# ActiTouch_Receiver_Sheet1.net
KiCad netlist of a schematic drawn in Altium Designer
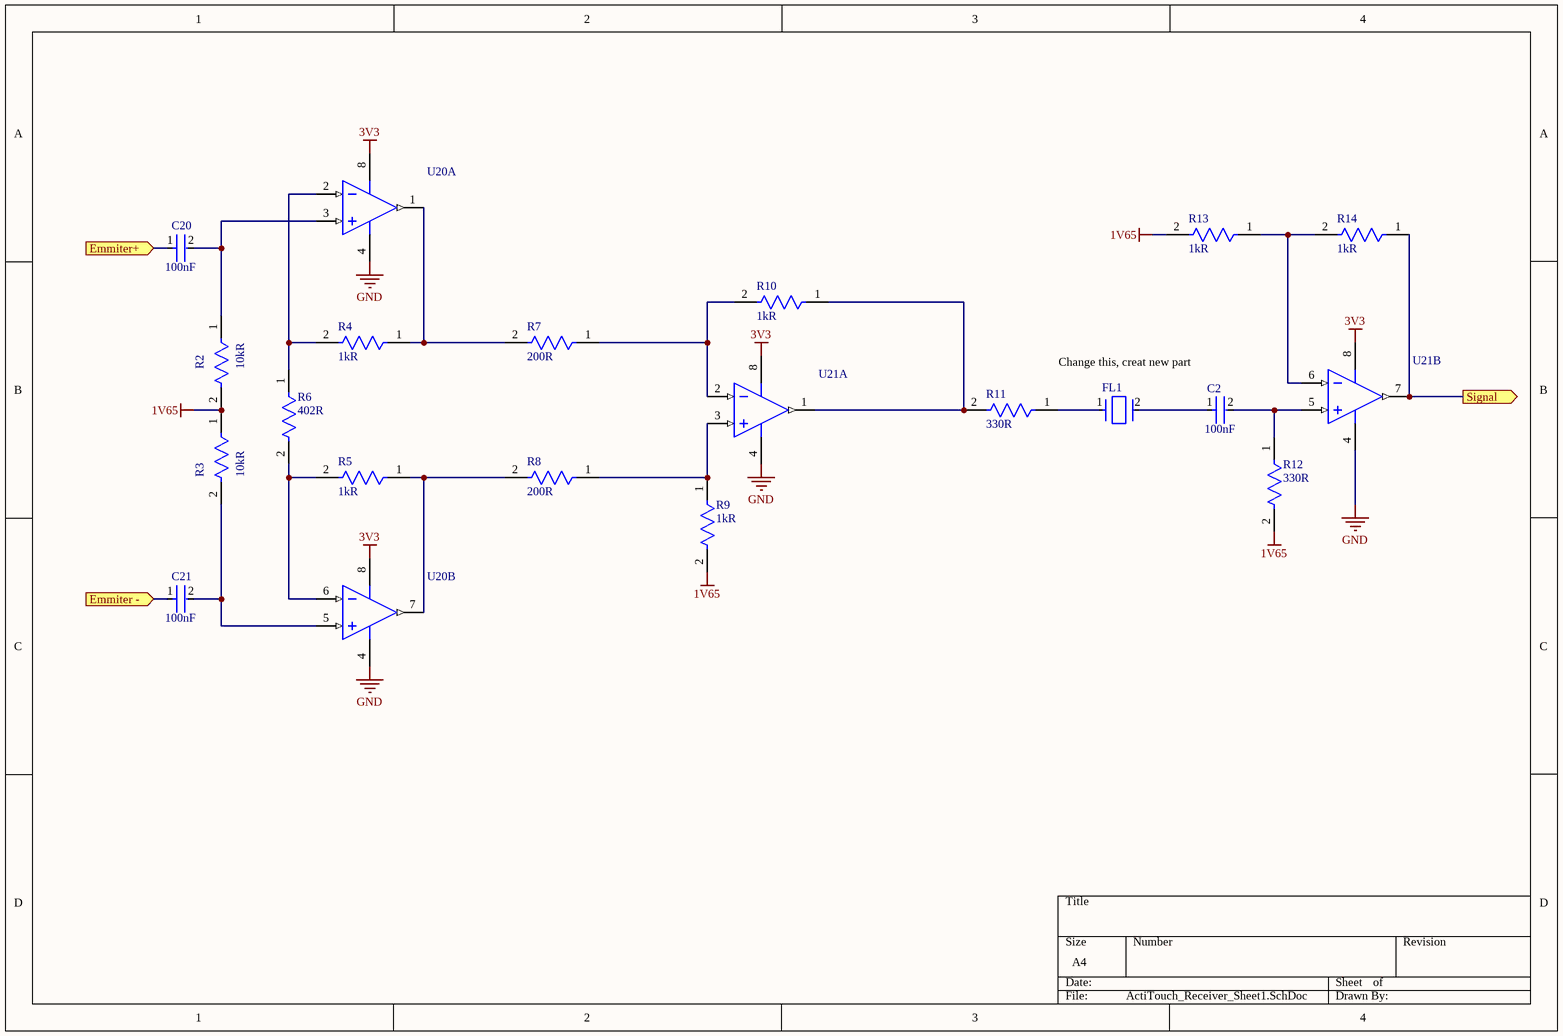
[diagram p0: ActiTouch_Receiver_Sheet1.SchDoc]

(export (version "E")
  (design (tool "Eeschema 10.0.6"))
  (components
    (comp (ref "C2")
      (value "EMK107B7104KAHT")
      (footprint "FP-0603-L_1_6_0_1-W_0_8_0-IPC_B")
      (description "None")
      (fields (field (name "CAPACITANCE") "100nF") (field (name "TOLERANCE") "10%"))
      (libsource (lib "Altium Content Vault") (part "02cd4be3c70576c341d710602a673aa"))
    )
    (comp (ref "C20")
      (value "EMK107B7104KAHT")
      (footprint "FP-0603-L_1_6_0_1-W_0_8_0-IPC_B")
      (description "None")
      (fields (field (name "CAPACITANCE") "100nF") (field (name "TOLERANCE") "10%"))
      (libsource (lib "Altium Content Vault") (part "02cd4be3c70576c341d710602a673aa"))
    )
    (comp (ref "C21")
      (value "EMK107B7104KAHT")
      (footprint "FP-0603-L_1_6_0_1-W_0_8_0-IPC_B")
      (description "None")
      (fields (field (name "CAPACITANCE") "100nF") (field (name "TOLERANCE") "10%"))
      (libsource (lib "Altium Content Vault") (part "02cd4be3c70576c341d710602a673aa"))
    )
    (comp (ref "FL1")
      (value "CDSCB10M7GA121-R0")
      (footprint "FP-CDSCB10M7GA121-R0-MFG")
      (description "Ceramic Filter 10.7MHz 2-Pin Surface Mount Emboss T/R")
      (libsource (lib "Altium Content Vault") (part "c23a69dc6c9e2f18f2079038eb95dd1"))
    )
    (comp (ref "R2")
      (value "ESR03EZPJ101")
      (footprint "FP-ESR03-MFG")
      (description "100Ω ±5% 0.25W 0603 Anti-Surge Chip Resistor AEC-Q200")
      (fields (field (name "TOLERANCE") "5%") (field (name "RESISTANCE") "10kR"))
      (libsource (lib "Altium Content Vault") (part "1029c3af85768c4190bb7ad29bc67b5"))
    )
    (comp (ref "R3")
      (value "ESR03EZPJ101")
      (footprint "FP-ESR03-MFG")
      (description "100Ω ±5% 0.25W 0603 Anti-Surge Chip Resistor AEC-Q200")
      (fields (field (name "TOLERANCE") "5%") (field (name "RESISTANCE") "10kR"))
      (libsource (lib "Altium Content Vault") (part "1029c3af85768c4190bb7ad29bc67b5"))
    )
    (comp (ref "R4")
      (value "ESR03EZPJ101")
      (footprint "FP-ESR03-MFG")
      (description "100Ω ±5% 0.25W 0603 Anti-Surge Chip Resistor AEC-Q200")
      (fields (field (name "TOLERANCE") "5%") (field (name "RESISTANCE") "1kR"))
      (libsource (lib "Altium Content Vault") (part "1029c3af85768c4190bb7ad29bc67b5"))
    )
    (comp (ref "R5")
      (value "ESR03EZPJ101")
      (footprint "FP-ESR03-MFG")
      (description "100Ω ±5% 0.25W 0603 Anti-Surge Chip Resistor AEC-Q200")
      (fields (field (name "TOLERANCE") "5%") (field (name "RESISTANCE") "1kR"))
      (libsource (lib "Altium Content Vault") (part "1029c3af85768c4190bb7ad29bc67b5"))
    )
    (comp (ref "R6")
      (value "ESR03EZPJ101")
      (footprint "FP-ESR03-MFG")
      (description "100Ω ±5% 0.25W 0603 Anti-Surge Chip Resistor AEC-Q200")
      (fields (field (name "TOLERANCE") "5%") (field (name "RESISTANCE") "402R"))
      (libsource (lib "Altium Content Vault") (part "1029c3af85768c4190bb7ad29bc67b5"))
    )
    (comp (ref "R7")
      (value "ESR03EZPJ101")
      (footprint "FP-ESR03-MFG")
      (description "100Ω ±5% 0.25W 0603 Anti-Surge Chip Resistor AEC-Q200")
      (fields (field (name "TOLERANCE") "5%") (field (name "RESISTANCE") "200R"))
      (libsource (lib "Altium Content Vault") (part "1029c3af85768c4190bb7ad29bc67b5"))
    )
    (comp (ref "R8")
      (value "ESR03EZPJ101")
      (footprint "FP-ESR03-MFG")
      (description "100Ω ±5% 0.25W 0603 Anti-Surge Chip Resistor AEC-Q200")
      (fields (field (name "TOLERANCE") "5%") (field (name "RESISTANCE") "200R"))
      (libsource (lib "Altium Content Vault") (part "1029c3af85768c4190bb7ad29bc67b5"))
    )
    (comp (ref "R9")
      (value "ESR03EZPJ101")
      (footprint "FP-ESR03-MFG")
      (description "100Ω ±5% 0.25W 0603 Anti-Surge Chip Resistor AEC-Q200")
      (fields (field (name "TOLERANCE") "5%") (field (name "RESISTANCE") "1kR"))
      (libsource (lib "Altium Content Vault") (part "1029c3af85768c4190bb7ad29bc67b5"))
    )
    (comp (ref "R10")
      (value "ESR03EZPJ101")
      (footprint "FP-ESR03-MFG")
      (description "100Ω ±5% 0.25W 0603 Anti-Surge Chip Resistor AEC-Q200")
      (fields (field (name "TOLERANCE") "5%") (field (name "RESISTANCE") "1kR"))
      (libsource (lib "Altium Content Vault") (part "1029c3af85768c4190bb7ad29bc67b5"))
    )
    (comp (ref "R11")
      (value "ESR03EZPJ101")
      (footprint "FP-ESR03-MFG")
      (description "100Ω ±5% 0.25W 0603 Anti-Surge Chip Resistor AEC-Q200")
      (fields (field (name "TOLERANCE") "5%") (field (name "RESISTANCE") "330R"))
      (libsource (lib "Altium Content Vault") (part "1029c3af85768c4190bb7ad29bc67b5"))
    )
    (comp (ref "R12")
      (value "ESR03EZPJ101")
      (footprint "FP-ESR03-MFG")
      (description "100Ω ±5% 0.25W 0603 Anti-Surge Chip Resistor AEC-Q200")
      (fields (field (name "TOLERANCE") "5%") (field (name "RESISTANCE") "330R"))
      (libsource (lib "Altium Content Vault") (part "1029c3af85768c4190bb7ad29bc67b5"))
    )
    (comp (ref "R13")
      (value "ESR03EZPJ101")
      (footprint "FP-ESR03-MFG")
      (description "100Ω ±5% 0.25W 0603 Anti-Surge Chip Resistor AEC-Q200")
      (fields (field (name "TOLERANCE") "5%") (field (name "RESISTANCE") "1kR"))
      (libsource (lib "Altium Content Vault") (part "1029c3af85768c4190bb7ad29bc67b5"))
    )
    (comp (ref "R14")
      (value "ESR03EZPJ101")
      (footprint "FP-ESR03-MFG")
      (description "100Ω ±5% 0.25W 0603 Anti-Surge Chip Resistor AEC-Q200")
      (fields (field (name "TOLERANCE") "5%") (field (name "RESISTANCE") "1kR"))
      (libsource (lib "Altium Content Vault") (part "1029c3af85768c4190bb7ad29bc67b5"))
    )
    (comp (ref "U20")
      (value "LTC6253IMS8#TRPBF")
      (footprint "LT-MS8-8_N")
      (fields
        (field (name "LINEAR TECHNOLOGY PART NUMBER") "LTC6253")
        (field (name "MANUFACTURER") "Linear Technology")
      )
      (libsource (lib "Altium Content Vault") (part "LT-LTC6253-MS8-8"))
    )
    (comp (ref "U21")
      (value "LTC6253IMS8#TRPBF")
      (footprint "LT-MS8-8_N")
      (fields
        (field (name "LINEAR TECHNOLOGY PART NUMBER") "LTC6253")
        (field (name "MANUFACTURER") "Linear Technology")
      )
      (libsource (lib "Altium Content Vault") (part "LT-LTC6253-MS8-8"))
    )
  )
  (nets
    (net (code "1") (name "/Emmiter -") (class "Default")
      (node (ref "C21") (pin "1") (pinfunction "1_1") (pintype "passive"))
    )
    (net (code "2") (name "/Emmiter+") (class "Default")
      (node (ref "C20") (pin "1") (pinfunction "1_1") (pintype "passive"))
    )
    (net (code "3") (name "/Signal") (class "Default")
      (node (ref "R14") (pin "1") (pinfunction "1_1") (pintype "passive"))
      (node (ref "U21") (pin "7") (pinfunction "OUT_B_7") (pintype "output"))
    )
    (net (code "4") (name "1V65") (class "Default")
      (node (ref "R12") (pin "2") (pinfunction "2_2") (pintype "passive"))
      (node (ref "R13") (pin "2") (pinfunction "2_2") (pintype "passive"))
      (node (ref "R2") (pin "2") (pinfunction "2_2") (pintype "passive"))
      (node (ref "R3") (pin "1") (pinfunction "1_1") (pintype "passive"))
      (node (ref "R9") (pin "2") (pinfunction "2_2") (pintype "passive"))
    )
    (net (code "5") (name "3V3") (class "Default")
      (node (ref "U20") (pin "8") (pinfunction "V+_8") (pintype "power_in"))
      (node (ref "U21") (pin "8") (pinfunction "V+_8") (pintype "power_in"))
    )
    (net (code "6") (name "GND") (class "Default")
      (node (ref "U20") (pin "4") (pinfunction "V-_4") (pintype "power_in"))
      (node (ref "U21") (pin "4") (pinfunction "V-_4") (pintype "power_in"))
    )
    (net (code "7") (name "Net-(C2-Pad1)") (class "Default")
      (node (ref "C2") (pin "1") (pinfunction "1_1") (pintype "passive"))
      (node (ref "FL1") (pin "2") (pinfunction "2_2") (pintype "passive"))
    )
    (net (code "8") (name "Net-(FL1-Pad1)") (class "Default")
      (node (ref "FL1") (pin "1") (pinfunction "1_1") (pintype "passive"))
      (node (ref "R11") (pin "1") (pinfunction "1_1") (pintype "passive"))
    )
    (net (code "9") (name "Net-(U20A-+IN_A)") (class "Default")
      (node (ref "C20") (pin "2") (pinfunction "2_2") (pintype "passive"))
      (node (ref "R2") (pin "1") (pinfunction "1_1") (pintype "passive"))
      (node (ref "U20") (pin "3") (pinfunction "+IN_A_3") (pintype "input"))
    )
    (net (code "10") (name "Net-(U20A--IN_A)") (class "Default")
      (node (ref "R4") (pin "2") (pinfunction "2_2") (pintype "passive"))
      (node (ref "R6") (pin "1") (pinfunction "1_1") (pintype "passive"))
      (node (ref "U20") (pin "2") (pinfunction "-IN_A_2") (pintype "input"))
    )
    (net (code "11") (name "Net-(U20A-OUT_A)") (class "Default")
      (node (ref "R4") (pin "1") (pinfunction "1_1") (pintype "passive"))
      (node (ref "R7") (pin "2") (pinfunction "2_2") (pintype "passive"))
      (node (ref "U20") (pin "1") (pinfunction "OUT_A_1") (pintype "output"))
    )
    (net (code "12") (name "Net-(U20B-+IN_B)") (class "Default")
      (node (ref "C21") (pin "2") (pinfunction "2_2") (pintype "passive"))
      (node (ref "R3") (pin "2") (pinfunction "2_2") (pintype "passive"))
      (node (ref "U20") (pin "5") (pinfunction "+IN_B_5") (pintype "input"))
    )
    (net (code "13") (name "Net-(U20B--IN_B)") (class "Default")
      (node (ref "R5") (pin "2") (pinfunction "2_2") (pintype "passive"))
      (node (ref "R6") (pin "2") (pinfunction "2_2") (pintype "passive"))
      (node (ref "U20") (pin "6") (pinfunction "-IN_B_6") (pintype "input"))
    )
    (net (code "14") (name "Net-(U20B-OUT_B)") (class "Default")
      (node (ref "R5") (pin "1") (pinfunction "1_1") (pintype "passive"))
      (node (ref "R8") (pin "2") (pinfunction "2_2") (pintype "passive"))
      (node (ref "U20") (pin "7") (pinfunction "OUT_B_7") (pintype "output"))
    )
    (net (code "15") (name "Net-(U21A-+IN_A)") (class "Default")
      (node (ref "R8") (pin "1") (pinfunction "1_1") (pintype "passive"))
      (node (ref "R9") (pin "1") (pinfunction "1_1") (pintype "passive"))
      (node (ref "U21") (pin "3") (pinfunction "+IN_A_3") (pintype "input"))
    )
    (net (code "16") (name "Net-(U21A--IN_A)") (class "Default")
      (node (ref "R10") (pin "2") (pinfunction "2_2") (pintype "passive"))
      (node (ref "R7") (pin "1") (pinfunction "1_1") (pintype "passive"))
      (node (ref "U21") (pin "2") (pinfunction "-IN_A_2") (pintype "input"))
    )
    (net (code "17") (name "Net-(U21A-OUT_A)") (class "Default")
      (node (ref "R10") (pin "1") (pinfunction "1_1") (pintype "passive"))
      (node (ref "R11") (pin "2") (pinfunction "2_2") (pintype "passive"))
      (node (ref "U21") (pin "1") (pinfunction "OUT_A_1") (pintype "output"))
    )
    (net (code "18") (name "Net-(U21B-+IN_B)") (class "Default")
      (node (ref "C2") (pin "2") (pinfunction "2_2") (pintype "passive"))
      (node (ref "R12") (pin "1") (pinfunction "1_1") (pintype "passive"))
      (node (ref "U21") (pin "5") (pinfunction "+IN_B_5") (pintype "input"))
    )
    (net (code "19") (name "Net-(U21B--IN_B)") (class "Default")
      (node (ref "R13") (pin "1") (pinfunction "1_1") (pintype "passive"))
      (node (ref "R14") (pin "2") (pinfunction "2_2") (pintype "passive"))
      (node (ref "U21") (pin "6") (pinfunction "-IN_B_6") (pintype "input"))
    )
  )
)
